# Power_Block.net
KiCad netlist of a schematic drawn in Altium Designer
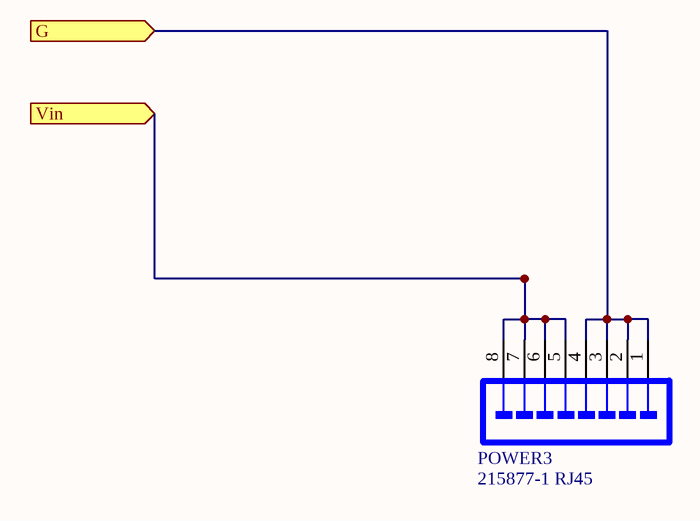
[diagram p0: Power_Block.SchDoc]

(export (version "E")
  (design (tool "Eeschema 10.0.6"))
  (components
    (comp (ref "POWER3")
      (value "215877-1 RJ45")
      (footprint "Mobile Robot__MainBord___Ms:Rj45_DS1127__HR911105A")
      (libsource (lib "test_Library11") (part "215877-1 RJ45"))
    )
  )
  (nets
    (net (code "1") (name "/G") (class "Default")
      (node (ref "POWER3") (pin "1") (pinfunction "1_1") (pintype "passive"))
      (node (ref "POWER3") (pin "2") (pinfunction "2_2") (pintype "passive"))
      (node (ref "POWER3") (pin "3") (pinfunction "3_3") (pintype "passive"))
      (node (ref "POWER3") (pin "4") (pinfunction "4_4") (pintype "passive"))
    )
    (net (code "2") (name "/Vin") (class "Default")
      (node (ref "POWER3") (pin "5") (pinfunction "5_5") (pintype "passive"))
      (node (ref "POWER3") (pin "6") (pinfunction "6_6") (pintype "passive"))
      (node (ref "POWER3") (pin "7") (pinfunction "7_7") (pintype "passive"))
      (node (ref "POWER3") (pin "8") (pinfunction "8_8") (pintype "passive"))
    )
  )
)
